# RocketometerPx_9DS0.net
KiCad netlist of a schematic drawn in EAGLE
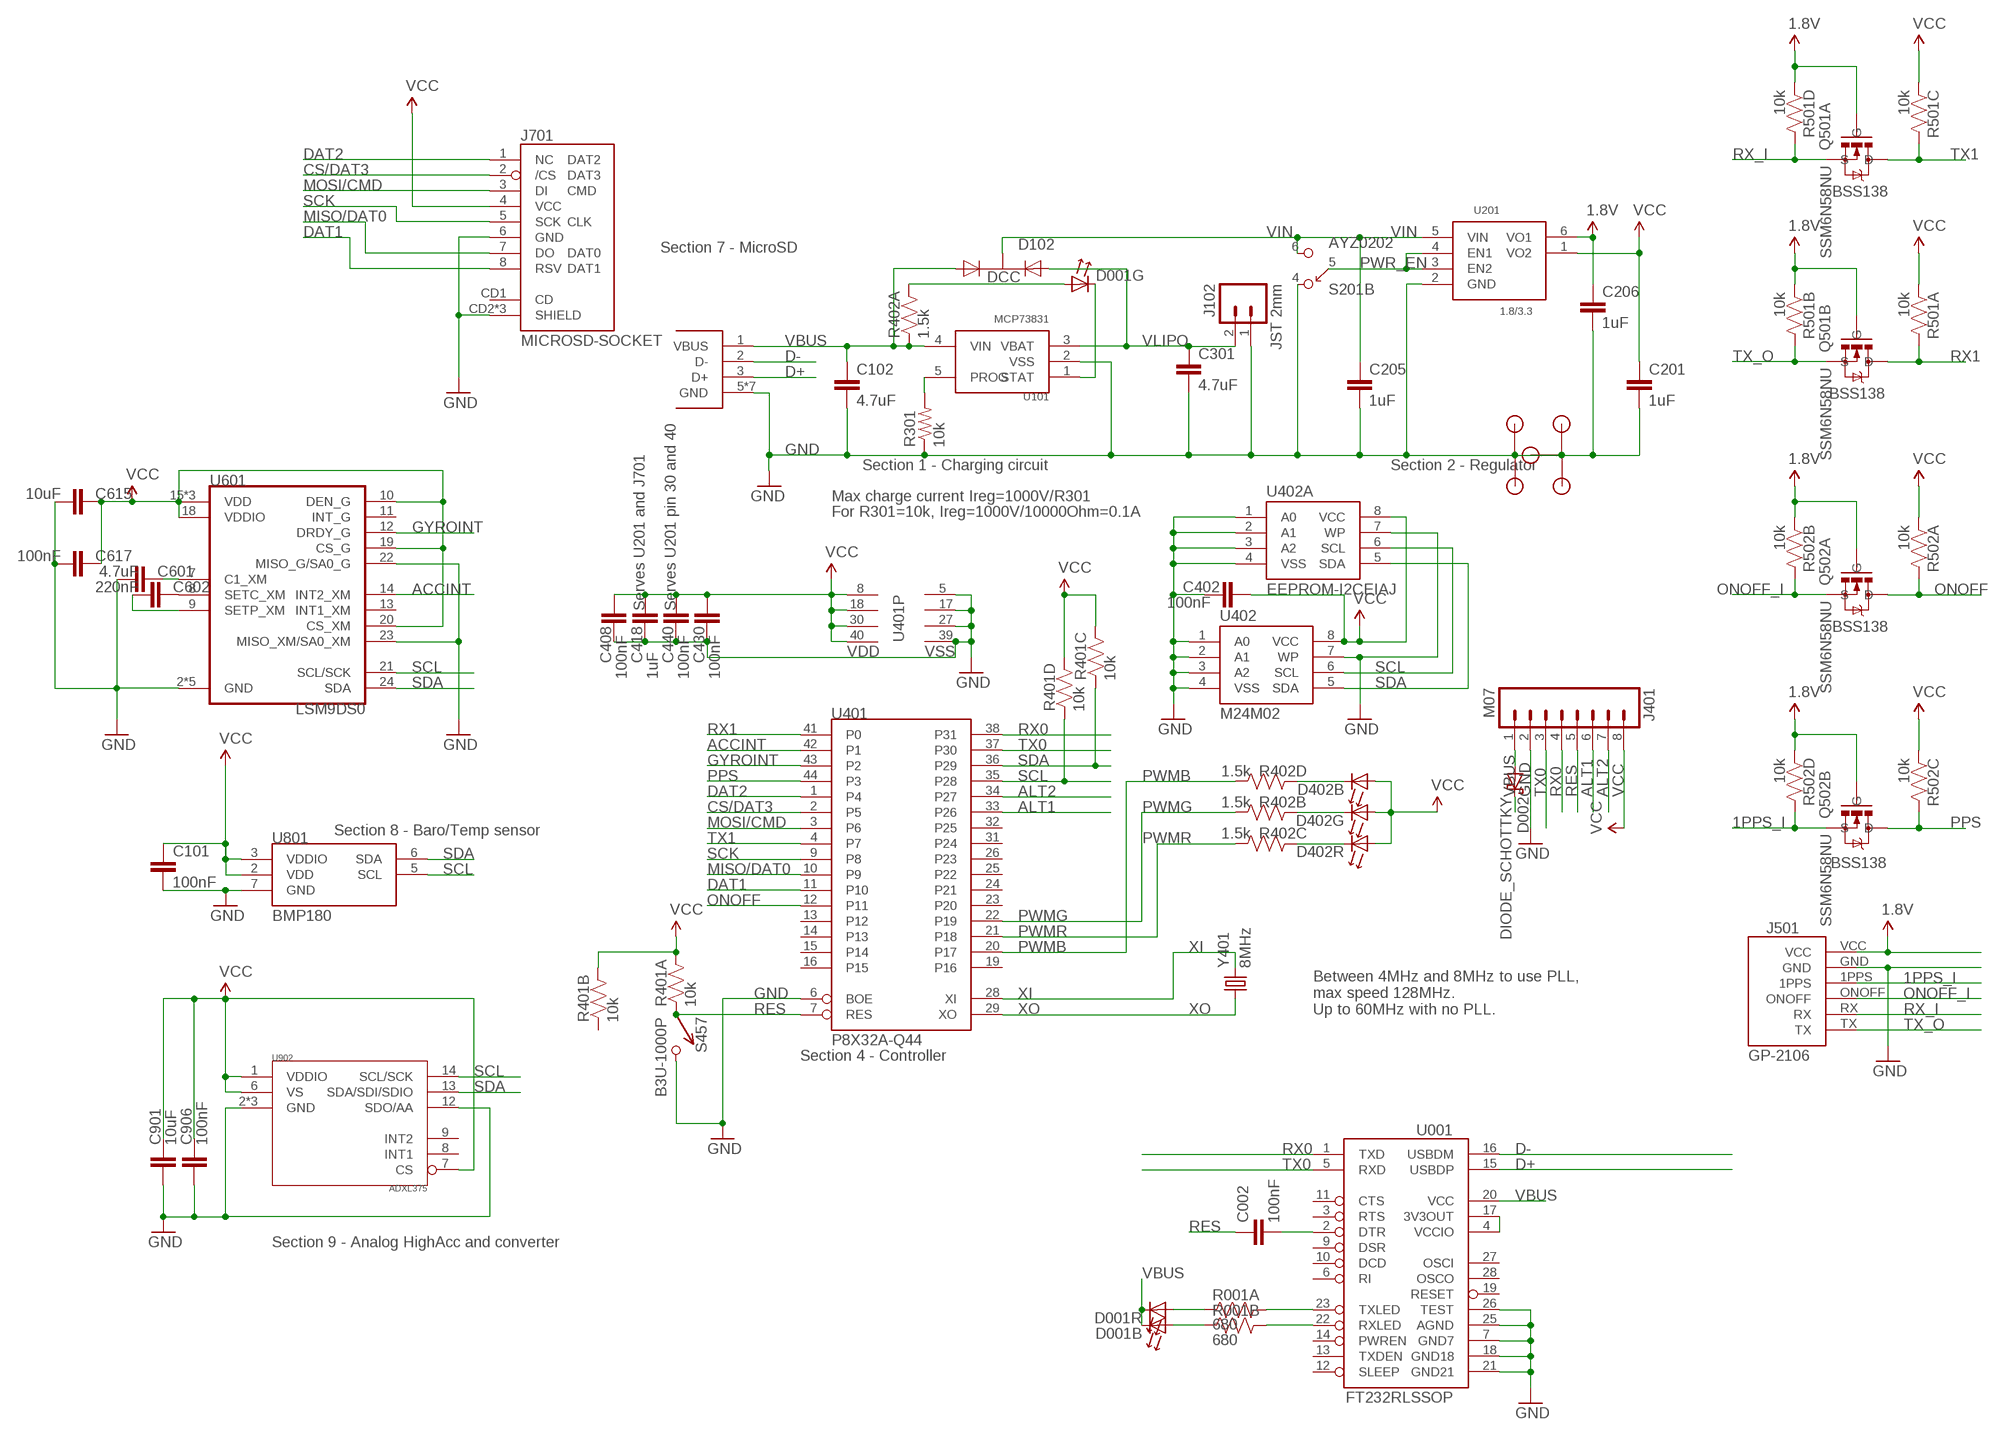
[diagram p0: schematic, sheet 1]

(export (version "E")
  (design (tool "Eeschema 10.0.6"))
  (components
    (comp (ref "C002")
      (value "100nF")
      (footprint "eagle-import:0402-CAP")
      (libsource (lib "eagle-import") (part "CAP0402-CAP"))
    )
    (comp (ref "C101")
      (value "100nF")
      (footprint "eagle-import:0402-CAP")
      (libsource (lib "eagle-import") (part "CAP0402-CAP"))
    )
    (comp (ref "C102")
      (value "4.7uF")
      (footprint "eagle-import:0402-CAP")
      (libsource (lib "eagle-import") (part "CAP0402-CAP"))
    )
    (comp (ref "C201")
      (value "1uF")
      (footprint "eagle-import:0402-CAP")
      (libsource (lib "eagle-import") (part "CAP0402-CAP"))
    )
    (comp (ref "C205")
      (value "1uF")
      (footprint "eagle-import:0402-CAP")
      (libsource (lib "eagle-import") (part "CAP0402-CAP"))
    )
    (comp (ref "C206")
      (value "1uF")
      (footprint "eagle-import:0402-CAP")
      (libsource (lib "eagle-import") (part "CAP0402-CAP"))
    )
    (comp (ref "C301")
      (value "4.7uF")
      (footprint "eagle-import:0402-CAP")
      (libsource (lib "eagle-import") (part "CAP0402-CAP"))
    )
    (comp (ref "C402")
      (value "100nF")
      (footprint "eagle-import:0402-CAP")
      (libsource (lib "eagle-import") (part "CAP0402-CAP"))
    )
    (comp (ref "C408")
      (value "100nF")
      (footprint "eagle-import:0402-CAP")
      (libsource (lib "eagle-import") (part "CAP0402-CAP"))
    )
    (comp (ref "C418")
      (value "1uF")
      (footprint "eagle-import:0402-CAP")
      (libsource (lib "eagle-import") (part "CAP0402-CAP"))
    )
    (comp (ref "C430")
      (value "100nF")
      (footprint "eagle-import:0402-CAP")
      (libsource (lib "eagle-import") (part "CAP0402-CAP"))
    )
    (comp (ref "C440")
      (value "100nF")
      (footprint "eagle-import:0402-CAP")
      (libsource (lib "eagle-import") (part "CAP0402-CAP"))
    )
    (comp (ref "C601")
      (value "4.7uF")
      (footprint "eagle-import:0402-CAP")
      (libsource (lib "eagle-import") (part "CAP0402-CAP"))
    )
    (comp (ref "C602")
      (value "220nF")
      (footprint "eagle-import:0402-CAP")
      (libsource (lib "eagle-import") (part "CAP0402-CAP"))
    )
    (comp (ref "C615")
      (value "10uF")
      (footprint "eagle-import:0603-CAP")
      (libsource (lib "eagle-import") (part "CAP0603-CAP"))
    )
    (comp (ref "C617")
      (value "100nF")
      (footprint "eagle-import:0402-CAP")
      (libsource (lib "eagle-import") (part "CAP0402-CAP"))
    )
    (comp (ref "C901")
      (value "10uF")
      (footprint "eagle-import:0603-CAP")
      (libsource (lib "eagle-import") (part "CAP0603-CAP"))
    )
    (comp (ref "C906")
      (value "100nF")
      (footprint "eagle-import:0402-CAP")
      (libsource (lib "eagle-import") (part "SparkFun-Passives_CAP0402-CAP"))
    )
    (comp (ref "D001")
      (value "SMLP36RGB2W(R)")
      (footprint "eagle-import:SMLP36")
      (libsource (lib "eagle-import") (part "SMLP36RGB2W(R)"))
    )
    (comp (ref "D002")
      (value "DIODE_SCHOTTKY")
      (footprint "eagle-import:D0603")
      (libsource (lib "eagle-import") (part "DIODE_SCHOTTKY"))
    )
    (comp (ref "D102")
      (value "DCC")
      (footprint "eagle-import:SOT-23-3")
      (libsource (lib "eagle-import") (part "PMEG2005CT"))
    )
    (comp (ref "D402")
      (value "SMLP36RGB2W(R)")
      (footprint "eagle-import:SMLP36")
      (libsource (lib "eagle-import") (part "SMLP36RGB2W(R)"))
    )
    (comp (ref "J001")
      (value "USB_MICROB_JSTFCI")
      (footprint "eagle-import:USB-MICROB-CONN-09505")
      (libsource (lib "eagle-import") (part "USB_MICROB_JSTFCI"))
    )
    (comp (ref "J102")
      (value "JST 2mm")
      (footprint "eagle-import:JST-2-SMD")
      (libsource (lib "eagle-import") (part "M02-JST-2MM-SMT"))
    )
    (comp (ref "J401")
      (value "M07")
      (footprint "eagle-import:M08SIP")
      (libsource (lib "eagle-import") (part "M08NOSILK"))
    )
    (comp (ref "J501")
      (value "GP-2106")
      (footprint "eagle-import:GP-2106")
      (libsource (lib "eagle-import") (part "GP-2106"))
    )
    (comp (ref "J701")
      (value "MICROSD-SOCKET")
      (footprint "eagle-import:MICROSD-SOCKET-PP")
      (libsource (lib "eagle-import") (part "MICROSD-SOCKET"))
    )
    (comp (ref "JP1")
      (value "STANDOFF")
      (footprint "eagle-import:STANDOFF")
      (libsource (lib "eagle-import") (part "STANDOFF"))
    )
    (comp (ref "JP2")
      (value "STANDOFF")
      (footprint "eagle-import:STANDOFF")
      (libsource (lib "eagle-import") (part "STANDOFF"))
    )
    (comp (ref "JP3")
      (value "STANDOFF")
      (footprint "eagle-import:STANDOFF")
      (libsource (lib "eagle-import") (part "STANDOFF"))
    )
    (comp (ref "JP4")
      (value "STANDOFF")
      (footprint "eagle-import:STANDOFF")
      (libsource (lib "eagle-import") (part "STANDOFF"))
    )
    (comp (ref "JP5")
      (value "STANDOFF")
      (footprint "eagle-import:STANDOFF")
      (libsource (lib "eagle-import") (part "STANDOFF"))
    )
    (comp (ref "Q501")
      (value "SSM6N58NU")
      (footprint "eagle-import:UDFN6")
      (libsource (lib "eagle-import") (part "SSM6N58NU"))
    )
    (comp (ref "Q502")
      (value "SSM6N58NU")
      (footprint "eagle-import:UDFN6")
      (libsource (lib "eagle-import") (part "SSM6N58NU"))
    )
    (comp (ref "R001")
      (value "680")
      (footprint "eagle-import:CRA02")
      (fields (field (name "DIGIKEY") "CRA4S8680CT-ND"))
      (libsource (lib "eagle-import") (part "RP2EXB24V"))
    )
    (comp (ref "R301")
      (value "10k")
      (footprint "eagle-import:0402-RES")
      (libsource (lib "eagle-import") (part "RESISTOR0402-RES"))
    )
    (comp (ref "R401")
      (value "10k")
      (footprint "eagle-import:CRA04")
      (fields (field (name "DIGIKEY") "CRA4S810KCT-ND"))
      (libsource (lib "eagle-import") (part "RP404"))
    )
    (comp (ref "R402")
      (value "1.5k")
      (footprint "eagle-import:CRA04")
      (fields (field (name "DIGIKEY") "CRA4S81.5KCT-ND"))
      (libsource (lib "eagle-import") (part "RP404"))
    )
    (comp (ref "R501")
      (value "10k")
      (footprint "eagle-import:CRA04")
      (fields (field (name "DIGIKEY") "CRA4S810KCT-ND"))
      (libsource (lib "eagle-import") (part "RP404"))
    )
    (comp (ref "R502")
      (value "10k")
      (footprint "eagle-import:CRA04")
      (fields (field (name "DIGIKEY") "CRA4S810KCT-ND"))
      (libsource (lib "eagle-import") (part "RP404"))
    )
    (comp (ref "S201")
      (value "AYZ0202")
      (footprint "eagle-import:AYZ0202")
      (libsource (lib "eagle-import") (part "AYZ0202"))
    )
    (comp (ref "S457")
      (value "B3U-1000P")
      (footprint "eagle-import:B3U-1000P")
      (libsource (lib "eagle-import") (part "B3U-1000P"))
    )
    (comp (ref "U001")
      (value "FT232RLSSOP")
      (footprint "eagle-import:SSOP28DB")
      (libsource (lib "eagle-import") (part "FT232RLSSOP"))
    )
    (comp (ref "U101")
      (value "MCP73831")
      (footprint "eagle-import:SOT-23-5")
      (libsource (lib "eagle-import") (part "MCP73831"))
    )
    (comp (ref "U201")
      (value "1.8/3.3")
      (footprint "eagle-import:SOT-23-6")
      (libsource (lib "eagle-import") (part "AP73X2"))
    )
    (comp (ref "U401")
      (value "P8X32A-Q44")
      (footprint "eagle-import:P8X32A-Q44")
      (fields (field (name "DIGIKEY") "P8X32A-Q44-ND"))
      (libsource (lib "eagle-import") (part "P8X32A-Q44"))
    )
    (comp (ref "U402")
      (value "M24M02")
      (footprint "eagle-import:SO8N")
      (libsource (lib "eagle-import") (part "EEPROM-I2C"))
    )
    (comp (ref "U402A")
      (value "EEPROM-I2CEIAJ")
      (footprint "eagle-import:SO08-EIAJ")
      (libsource (lib "eagle-import") (part "EEPROM-I2CEIAJ"))
    )
    (comp (ref "U601")
      (value "LSM9DS0")
      (footprint "eagle-import:LGA24_LSM")
      (libsource (lib "eagle-import") (part "LSM9DS0"))
    )
    (comp (ref "U801")
      (value "BMP180")
      (footprint "eagle-import:BMP180")
      (libsource (lib "eagle-import") (part "BMP180"))
    )
    (comp (ref "U902")
      (value "ADXL375")
      (footprint "eagle-import:ADXL375")
      (libsource (lib "eagle-import") (part "ADXL375"))
    )
    (comp (ref "Y401")
      (value "8MHz")
      (footprint "eagle-import:CRYSTAL_SMD_3_2MM_2_5MM")
      (libsource (lib "eagle-import") (part "NX3225GD"))
    )
  )
  (nets
    (net (code "1") (name "/1PPS_I") (class "Default")
      (node (ref "J501") (pin "1PPS") (pinfunction "1PPS_1PPS") (pintype "bidirectional"))
      (node (ref "Q502") (pin "4") (pinfunction "S_4") (pintype "passive"))
      (node (ref "R502") (pin "5") (pinfunction "2_5") (pintype "passive"))
    )
    (net (code "2") (name "/ACCINT") (class "Default")
      (node (ref "U401") (pin "42") (pinfunction "P1_42") (pintype "bidirectional"))
      (node (ref "U601") (pin "14") (pinfunction "INT2_XM_14") (pintype "bidirectional"))
    )
    (net (code "3") (name "/ALT1") (class "Default")
      (node (ref "J401") (pin "6") (pinfunction "6_6") (pintype "passive"))
      (node (ref "U401") (pin "33") (pinfunction "P26_33") (pintype "bidirectional"))
    )
    (net (code "4") (name "/ALT2") (class "Default")
      (node (ref "J401") (pin "7") (pinfunction "7_7") (pintype "passive"))
      (node (ref "U401") (pin "34") (pinfunction "P27_34") (pintype "bidirectional"))
    )
    (net (code "5") (name "/CS{slash}DAT3") (class "Default")
      (node (ref "J701") (pin "2") (pinfunction "/CS_2") (pintype "bidirectional"))
      (node (ref "U401") (pin "2") (pinfunction "P5_2") (pintype "bidirectional"))
    )
    (net (code "6") (name "/D+") (class "Default")
      (node (ref "J001") (pin "3") (pinfunction "D+_3") (pintype "bidirectional"))
      (node (ref "U001") (pin "15") (pinfunction "USBDP_15") (pintype "bidirectional"))
    )
    (net (code "7") (name "/D-") (class "Default")
      (node (ref "J001") (pin "2") (pinfunction "D-_2") (pintype "bidirectional"))
      (node (ref "U001") (pin "16") (pinfunction "USBDM_16") (pintype "bidirectional"))
    )
    (net (code "8") (name "/DAT1") (class "Default")
      (node (ref "J701") (pin "8") (pinfunction "RSV_8") (pintype "bidirectional"))
      (node (ref "U401") (pin "11") (pinfunction "P10_11") (pintype "bidirectional"))
    )
    (net (code "9") (name "/DAT2") (class "Default")
      (node (ref "J701") (pin "1") (pinfunction "NC_1") (pintype "bidirectional"))
      (node (ref "U401") (pin "1") (pinfunction "P4_1") (pintype "bidirectional"))
    )
    (net (code "10") (name "/GYROINT") (class "Default")
      (node (ref "U401") (pin "43") (pinfunction "P2_43") (pintype "bidirectional"))
      (node (ref "U601") (pin "12") (pinfunction "DRDY_G_12") (pintype "bidirectional"))
    )
    (net (code "11") (name "/MISO{slash}DAT0") (class "Default")
      (node (ref "J701") (pin "7") (pinfunction "DO_7") (pintype "bidirectional"))
      (node (ref "U401") (pin "10") (pinfunction "P9_10") (pintype "bidirectional"))
    )
    (net (code "12") (name "/MOSI{slash}CMD") (class "Default")
      (node (ref "J701") (pin "3") (pinfunction "DI_3") (pintype "bidirectional"))
      (node (ref "U401") (pin "3") (pinfunction "P6_3") (pintype "bidirectional"))
    )
    (net (code "13") (name "/ONOFF") (class "Default")
      (node (ref "Q502") (pin "6") (pinfunction "D_6") (pintype "passive"))
      (node (ref "R502") (pin "8") (pinfunction "2_8") (pintype "passive"))
      (node (ref "U401") (pin "12") (pinfunction "P11_12") (pintype "bidirectional"))
    )
    (net (code "14") (name "/ONOFF_I") (class "Default")
      (node (ref "J501") (pin "ONOFF") (pinfunction "ONOFF_ONOFF") (pintype "bidirectional"))
      (node (ref "Q502") (pin "1") (pinfunction "S_1") (pintype "passive"))
      (node (ref "R502") (pin "7") (pinfunction "2_7") (pintype "passive"))
    )
    (net (code "15") (name "/PPS") (class "Default")
      (node (ref "Q502") (pin "3") (pinfunction "D_3") (pintype "passive"))
      (node (ref "R502") (pin "6") (pinfunction "2_6") (pintype "passive"))
      (node (ref "U401") (pin "44") (pinfunction "P3_44") (pintype "bidirectional"))
    )
    (net (code "16") (name "/PWMB") (class "Default")
      (node (ref "R402") (pin "4") (pinfunction "1_4") (pintype "passive"))
      (node (ref "U401") (pin "20") (pinfunction "P17_20") (pintype "bidirectional"))
    )
    (net (code "17") (name "/PWMG") (class "Default")
      (node (ref "R402") (pin "2") (pinfunction "1_2") (pintype "passive"))
      (node (ref "U401") (pin "22") (pinfunction "P19_22") (pintype "bidirectional"))
    )
    (net (code "18") (name "/PWMR") (class "Default")
      (node (ref "R402") (pin "3") (pinfunction "1_3") (pintype "passive"))
      (node (ref "U401") (pin "21") (pinfunction "P18_21") (pintype "bidirectional"))
    )
    (net (code "19") (name "/PWR_EN") (class "Default")
      (node (ref "S201") (pin "5") (pinfunction "P$3_5") (pintype "bidirectional"))
      (node (ref "U201") (pin "3") (pinfunction "EN2_3") (pintype "bidirectional"))
      (node (ref "U201") (pin "4") (pinfunction "EN1_4") (pintype "bidirectional"))
    )
    (net (code "20") (name "/RES") (class "Default")
      (node (ref "C002") (pin "1") (pinfunction "1_1") (pintype "passive"))
      (node (ref "J401") (pin "5") (pinfunction "5_5") (pintype "passive"))
      (node (ref "R401") (pin "1") (pinfunction "1_1") (pintype "passive"))
      (node (ref "S457") (pin "P$1") (pinfunction "1_P$1") (pintype "bidirectional"))
      (node (ref "U401") (pin "7") (pinfunction "RES_7") (pintype "bidirectional"))
    )
    (net (code "21") (name "/RX0") (class "Default")
      (node (ref "J401") (pin "4") (pinfunction "4_4") (pintype "passive"))
      (node (ref "U001") (pin "1") (pinfunction "TXD_1") (pintype "output"))
      (node (ref "U401") (pin "38") (pinfunction "P31_38") (pintype "bidirectional"))
    )
    (net (code "22") (name "/RX1") (class "Default")
      (node (ref "Q501") (pin "3") (pinfunction "D_3") (pintype "passive"))
      (node (ref "R501") (pin "8") (pinfunction "2_8") (pintype "passive"))
      (node (ref "U401") (pin "41") (pinfunction "P0_41") (pintype "bidirectional"))
    )
    (net (code "23") (name "/RX_I") (class "Default")
      (node (ref "J501") (pin "RX") (pinfunction "RX_RX") (pintype "bidirectional"))
      (node (ref "Q501") (pin "1") (pinfunction "S_1") (pintype "passive"))
      (node (ref "R501") (pin "5") (pinfunction "2_5") (pintype "passive"))
    )
    (net (code "24") (name "/SCK") (class "Default")
      (node (ref "J701") (pin "5") (pinfunction "SCK_5") (pintype "bidirectional"))
      (node (ref "U401") (pin "9") (pinfunction "P8_9") (pintype "bidirectional"))
    )
    (net (code "25") (name "/SCL") (class "Default")
      (node (ref "R401") (pin "4") (pinfunction "1_4") (pintype "passive"))
      (node (ref "U401") (pin "35") (pinfunction "P28_35") (pintype "bidirectional"))
      (node (ref "U402") (pin "6") (pinfunction "SCL_6") (pintype "bidirectional"))
      (node (ref "U402A") (pin "6") (pinfunction "SCL_6") (pintype "bidirectional"))
      (node (ref "U601") (pin "21") (pinfunction "SCL/SCK_21") (pintype "bidirectional"))
      (node (ref "U801") (pin "5") (pinfunction "SCL_5") (pintype "input"))
      (node (ref "U902") (pin "14") (pinfunction "SCL/SCK_14") (pintype "input"))
    )
    (net (code "26") (name "/SDA") (class "Default")
      (node (ref "R401") (pin "3") (pinfunction "1_3") (pintype "passive"))
      (node (ref "U401") (pin "36") (pinfunction "P29_36") (pintype "bidirectional"))
      (node (ref "U402") (pin "5") (pinfunction "SDA_5") (pintype "bidirectional"))
      (node (ref "U402A") (pin "5") (pinfunction "SDA_5") (pintype "bidirectional"))
      (node (ref "U601") (pin "24") (pinfunction "SDA_24") (pintype "bidirectional"))
      (node (ref "U801") (pin "6") (pinfunction "SDA_6") (pintype "bidirectional"))
      (node (ref "U902") (pin "13") (pinfunction "SDA/SDI/SDIO_13") (pintype "bidirectional"))
    )
    (net (code "27") (name "/TX0") (class "Default")
      (node (ref "J401") (pin "3") (pinfunction "3_3") (pintype "passive"))
      (node (ref "U001") (pin "5") (pinfunction "RXD_5") (pintype "input"))
      (node (ref "U401") (pin "37") (pinfunction "P30_37") (pintype "bidirectional"))
    )
    (net (code "28") (name "/TX1") (class "Default")
      (node (ref "Q501") (pin "6") (pinfunction "D_6") (pintype "passive"))
      (node (ref "R501") (pin "6") (pinfunction "2_6") (pintype "passive"))
      (node (ref "U401") (pin "4") (pinfunction "P7_4") (pintype "bidirectional"))
    )
    (net (code "29") (name "/TX_O") (class "Default")
      (node (ref "J501") (pin "TX") (pinfunction "TX_TX") (pintype "bidirectional"))
      (node (ref "Q501") (pin "4") (pinfunction "S_4") (pintype "passive"))
      (node (ref "R501") (pin "7") (pinfunction "2_7") (pintype "passive"))
    )
    (net (code "30") (name "/VBUS") (class "Default")
      (node (ref "C102") (pin "1") (pinfunction "1_1") (pintype "passive"))
      (node (ref "D001") (pin "1") (pinfunction "C_1") (pintype "passive"))
      (node (ref "D001") (pin "3") (pinfunction "C_3") (pintype "passive"))
      (node (ref "D002") (pin "C") (pinfunction "K_C") (pintype "passive"))
      (node (ref "D102") (pin "1") (pinfunction "A1_1") (pintype "passive"))
      (node (ref "J001") (pin "1") (pinfunction "VBUS_1") (pintype "bidirectional"))
      (node (ref "R402") (pin "1") (pinfunction "1_1") (pintype "passive"))
      (node (ref "U001") (pin "20") (pinfunction "VCC_20") (pintype "power_in"))
      (node (ref "U101") (pin "4") (pinfunction "VIN_4") (pintype "power_in"))
    )
    (net (code "31") (name "/VIN") (class "Default")
      (node (ref "C205") (pin "1") (pinfunction "1_1") (pintype "passive"))
      (node (ref "D102") (pin "3") (pinfunction "K_3") (pintype "passive"))
      (node (ref "S201") (pin "6") (pinfunction "P$2_6") (pintype "bidirectional"))
      (node (ref "U201") (pin "5") (pinfunction "VIN_5") (pintype "bidirectional"))
    )
    (net (code "32") (name "/VLIPO") (class "Default")
      (node (ref "C301") (pin "1") (pinfunction "1_1") (pintype "passive"))
      (node (ref "D102") (pin "2") (pinfunction "A2_2") (pintype "passive"))
      (node (ref "J102") (pin "2") (pinfunction "2_2") (pintype "passive"))
      (node (ref "U101") (pin "3") (pinfunction "VBAT_3") (pintype "power_in"))
    )
    (net (code "33") (name "/XI") (class "Default")
      (node (ref "U401") (pin "28") (pinfunction "XI_28") (pintype "input"))
      (node (ref "Y401") (pin "2") (pinfunction "2_2") (pintype "passive"))
    )
    (net (code "34") (name "/XO") (class "Default")
      (node (ref "U401") (pin "29") (pinfunction "XO_29") (pintype "output"))
      (node (ref "Y401") (pin "1") (pinfunction "1_1") (pintype "passive"))
    )
    (net (code "35") (name "1.8V") (class "Default")
      (node (ref "C206") (pin "1") (pinfunction "1_1") (pintype "passive"))
      (node (ref "J501") (pin "VCC") (pinfunction "VCC_VCC") (pintype "bidirectional"))
      (node (ref "Q501") (pin "2") (pinfunction "G_2") (pintype "passive"))
      (node (ref "Q501") (pin "5") (pinfunction "G_5") (pintype "passive"))
      (node (ref "Q502") (pin "2") (pinfunction "G_2") (pintype "passive"))
      (node (ref "Q502") (pin "5") (pinfunction "G_5") (pintype "passive"))
      (node (ref "R501") (pin "2") (pinfunction "1_2") (pintype "passive"))
      (node (ref "R501") (pin "4") (pinfunction "1_4") (pintype "passive"))
      (node (ref "R502") (pin "2") (pinfunction "1_2") (pintype "passive"))
      (node (ref "R502") (pin "4") (pinfunction "1_4") (pintype "passive"))
      (node (ref "U201") (pin "6") (pinfunction "VO1_6") (pintype "bidirectional"))
    )
    (net (code "36") (name "GND") (class "Default")
      (node (ref "C101") (pin "2") (pinfunction "2_2") (pintype "passive"))
      (node (ref "C102") (pin "2") (pinfunction "2_2") (pintype "passive"))
      (node (ref "C201") (pin "2") (pinfunction "2_2") (pintype "passive"))
      (node (ref "C205") (pin "2") (pinfunction "2_2") (pintype "passive"))
      (node (ref "C206") (pin "2") (pinfunction "2_2") (pintype "passive"))
      (node (ref "C301") (pin "2") (pinfunction "2_2") (pintype "passive"))
      (node (ref "C402") (pin "2") (pinfunction "2_2") (pintype "passive"))
      (node (ref "C408") (pin "2") (pinfunction "2_2") (pintype "passive"))
      (node (ref "C418") (pin "2") (pinfunction "2_2") (pintype "passive"))
      (node (ref "C430") (pin "2") (pinfunction "2_2") (pintype "passive"))
      (node (ref "C440") (pin "2") (pinfunction "2_2") (pintype "passive"))
      (node (ref "C601") (pin "2") (pinfunction "2_2") (pintype "passive"))
      (node (ref "C615") (pin "1") (pinfunction "1_1") (pintype "passive"))
      (node (ref "C617") (pin "1") (pinfunction "1_1") (pintype "passive"))
      (node (ref "C901") (pin "2") (pinfunction "2_2") (pintype "passive"))
      (node (ref "C906") (pin "2") (pinfunction "2_2") (pintype "passive"))
      (node (ref "J001") (pin "5") (pinfunction "GND_5") (pintype "bidirectional"))
      (node (ref "J001") (pin "P1") (pinfunction "GND_P1") (pintype "bidirectional"))
      (node (ref "J001") (pin "P2") (pinfunction "GND_P2") (pintype "bidirectional"))
      (node (ref "J001") (pin "P3") (pinfunction "GND_P3") (pintype "bidirectional"))
      (node (ref "J001") (pin "P4") (pinfunction "GND_P4") (pintype "bidirectional"))
      (node (ref "J001") (pin "P5") (pinfunction "GND_P5") (pintype "bidirectional"))
      (node (ref "J001") (pin "P6") (pinfunction "GND_P6") (pintype "bidirectional"))
      (node (ref "J102") (pin "1") (pinfunction "1_1") (pintype "passive"))
      (node (ref "J401") (pin "2") (pinfunction "2_2") (pintype "passive"))
      (node (ref "J501") (pin "GND") (pinfunction "GND_GND") (pintype "bidirectional"))
      (node (ref "J701") (pin "6") (pinfunction "GND_6") (pintype "bidirectional"))
      (node (ref "J701") (pin "CD2") (pinfunction "SHIELD_CD2") (pintype "bidirectional"))
      (node (ref "J701") (pin "GND1") (pinfunction "SHIELD_GND1") (pintype "bidirectional"))
      (node (ref "J701") (pin "GND3") (pinfunction "SHIELD_GND3") (pintype "bidirectional"))
      (node (ref "JP1") (pin "P$1") (pinfunction "P$1_P$1") (pintype "bidirectional"))
      (node (ref "JP2") (pin "P$1") (pinfunction "P$1_P$1") (pintype "bidirectional"))
      (node (ref "JP3") (pin "P$1") (pinfunction "P$1_P$1") (pintype "bidirectional"))
      (node (ref "JP4") (pin "P$1") (pinfunction "P$1_P$1") (pintype "bidirectional"))
      (node (ref "JP5") (pin "P$1") (pinfunction "P$1_P$1") (pintype "bidirectional"))
      (node (ref "R301") (pin "1") (pinfunction "1_1") (pintype "passive"))
      (node (ref "S201") (pin "4") (pinfunction "P$1_4") (pintype "bidirectional"))
      (node (ref "S457") (pin "P$2") (pinfunction "2_P$2") (pintype "bidirectional"))
      (node (ref "U001") (pin "18") (pinfunction "GND18_18") (pintype "power_in"))
      (node (ref "U001") (pin "21") (pinfunction "GND21_21") (pintype "power_in"))
      (node (ref "U001") (pin "25") (pinfunction "AGND_25") (pintype "power_in"))
      (node (ref "U001") (pin "26") (pinfunction "TEST_26") (pintype "input"))
      (node (ref "U001") (pin "7") (pinfunction "GND7_7") (pintype "power_in"))
      (node (ref "U101") (pin "2") (pinfunction "VSS_2") (pintype "power_in"))
      (node (ref "U201") (pin "2") (pinfunction "GND_2") (pintype "bidirectional"))
      (node (ref "U401") (pin "17") (pinfunction "VSS_17") (pintype "power_in"))
      (node (ref "U401") (pin "27") (pinfunction "VSS_27") (pintype "power_in"))
      (node (ref "U401") (pin "39") (pinfunction "VSS_39") (pintype "power_in"))
      (node (ref "U401") (pin "5") (pinfunction "VSS_5") (pintype "power_in"))
      (node (ref "U401") (pin "6") (pinfunction "BOE_6") (pintype "input"))
      (node (ref "U402") (pin "1") (pinfunction "A0_1") (pintype "bidirectional"))
      (node (ref "U402") (pin "2") (pinfunction "A1_2") (pintype "bidirectional"))
      (node (ref "U402") (pin "3") (pinfunction "A2_3") (pintype "bidirectional"))
      (node (ref "U402") (pin "4") (pinfunction "VSS_4") (pintype "power_in"))
      (node (ref "U402") (pin "7") (pinfunction "WP_7") (pintype "bidirectional"))
      (node (ref "U402A") (pin "1") (pinfunction "A0_1") (pintype "bidirectional"))
      (node (ref "U402A") (pin "2") (pinfunction "A1_2") (pintype "bidirectional"))
      (node (ref "U402A") (pin "3") (pinfunction "A2_3") (pintype "bidirectional"))
      (node (ref "U402A") (pin "4") (pinfunction "VSS_4") (pintype "power_in"))
      (node (ref "U402A") (pin "7") (pinfunction "WP_7") (pintype "bidirectional"))
      (node (ref "U601") (pin "2") (pinfunction "GND_2") (pintype "power_in"))
      (node (ref "U601") (pin "22") (pinfunction "MISO_G/SA0_G_22") (pintype "bidirectional"))
      (node (ref "U601") (pin "23") (pinfunction "MISO_XM/SA0_XM_23") (pintype "bidirectional"))
      (node (ref "U601") (pin "3") (pinfunction "GND_3") (pintype "power_in"))
      (node (ref "U601") (pin "4") (pinfunction "GND_4") (pintype "power_in"))
      (node (ref "U601") (pin "5") (pinfunction "GND_5") (pintype "power_in"))
      (node (ref "U601") (pin "6") (pinfunction "GND_6") (pintype "power_in"))
      (node (ref "U801") (pin "7") (pinfunction "GND_7") (pintype "power_in"))
      (node (ref "U902") (pin "12") (pinfunction "SDO/AA_12") (pintype "bidirectional"))
      (node (ref "U902") (pin "2") (pinfunction "GND_2") (pintype "power_in"))
      (node (ref "U902") (pin "4") (pinfunction "GND_4") (pintype "power_in"))
      (node (ref "U902") (pin "5") (pinfunction "GND_5") (pintype "power_in"))
    )
    (net (code "37") (name "Net-(D001A-A)") (class "Default")
      (node (ref "D001") (pin "2") (pinfunction "A_2") (pintype "passive"))
      (node (ref "R001") (pin "2") (pinfunction "1_2") (pintype "passive"))
    )
    (net (code "38") (name "Net-(D001B-A)") (class "Default")
      (node (ref "D001") (pin "6") (pinfunction "A_6") (pintype "passive"))
      (node (ref "R402") (pin "8") (pinfunction "2_8") (pintype "passive"))
    )
    (net (code "39") (name "Net-(D001B-C)") (class "Default")
      (node (ref "D001") (pin "5") (pinfunction "C_5") (pintype "passive"))
      (node (ref "U101") (pin "1") (pinfunction "STAT_1") (pintype "bidirectional"))
    )
    (net (code "40") (name "Net-(D001C-A)") (class "Default")
      (node (ref "D001") (pin "4") (pinfunction "A_4") (pintype "passive"))
      (node (ref "R001") (pin "1") (pinfunction "1_1") (pintype "passive"))
    )
    (net (code "41") (name "Net-(D002-PadA)") (class "Default")
      (node (ref "D002") (pin "A") (pinfunction "A_A") (pintype "passive"))
      (node (ref "J401") (pin "1") (pinfunction "1_1") (pintype "passive"))
    )
    (net (code "42") (name "Net-(D402A-C)") (class "Default")
      (node (ref "D402") (pin "1") (pinfunction "C_1") (pintype "passive"))
      (node (ref "R402") (pin "5") (pinfunction "2_5") (pintype "passive"))
    )
    (net (code "43") (name "Net-(D402B-C)") (class "Default")
      (node (ref "D402") (pin "5") (pinfunction "C_5") (pintype "passive"))
      (node (ref "R402") (pin "7") (pinfunction "2_7") (pintype "passive"))
    )
    (net (code "44") (name "Net-(D402C-C)") (class "Default")
      (node (ref "D402") (pin "3") (pinfunction "C_3") (pintype "passive"))
      (node (ref "R402") (pin "6") (pinfunction "2_6") (pintype "passive"))
    )
    (net (code "45") (name "Net-(R001A-2)") (class "Default")
      (node (ref "R001") (pin "4") (pinfunction "2_4") (pintype "passive"))
      (node (ref "U001") (pin "23") (pinfunction "TXLED_23") (pintype "input"))
    )
    (net (code "46") (name "Net-(R001B-2)") (class "Default")
      (node (ref "R001") (pin "3") (pinfunction "2_3") (pintype "passive"))
      (node (ref "U001") (pin "22") (pinfunction "RXLED_22") (pintype "input"))
    )
    (net (code "47") (name "Net-(U001-3V3OUT)") (class "Default")
      (node (ref "U001") (pin "17") (pinfunction "3V3OUT_17") (pintype "output"))
      (node (ref "U001") (pin "4") (pinfunction "VCCIO_4") (pintype "power_in"))
    )
    (net (code "48") (name "Net-(U001-DTR)") (class "Default")
      (node (ref "C002") (pin "2") (pinfunction "2_2") (pintype "passive"))
      (node (ref "U001") (pin "2") (pinfunction "DTR_2") (pintype "output"))
    )
    (net (code "49") (name "Net-(U101-PROG)") (class "Default")
      (node (ref "R301") (pin "2") (pinfunction "2_2") (pintype "passive"))
      (node (ref "U101") (pin "5") (pinfunction "PROG_5") (pintype "passive"))
    )
    (net (code "50") (name "Net-(U601-C1_XM)") (class "Default")
      (node (ref "C601") (pin "1") (pinfunction "1_1") (pintype "passive"))
      (node (ref "U601") (pin "7") (pinfunction "C1_XM_7") (pintype "passive"))
    )
    (net (code "51") (name "Net-(U601-SETC_XM)") (class "Default")
      (node (ref "C602") (pin "1") (pinfunction "1_1") (pintype "passive"))
      (node (ref "U601") (pin "8") (pinfunction "SETC_XM_8") (pintype "passive"))
    )
    (net (code "52") (name "Net-(U601-SETP_XM)") (class "Default")
      (node (ref "C602") (pin "2") (pinfunction "2_2") (pintype "passive"))
      (node (ref "U601") (pin "9") (pinfunction "SETP_XM_9") (pintype "passive"))
    )
    (net (code "53") (name "VCC") (class "Default")
      (node (ref "C101") (pin "1") (pinfunction "1_1") (pintype "passive"))
      (node (ref "C201") (pin "1") (pinfunction "1_1") (pintype "passive"))
      (node (ref "C402") (pin "1") (pinfunction "1_1") (pintype "passive"))
      (node (ref "C408") (pin "1") (pinfunction "1_1") (pintype "passive"))
      (node (ref "C418") (pin "1") (pinfunction "1_1") (pintype "passive"))
      (node (ref "C430") (pin "1") (pinfunction "1_1") (pintype "passive"))
      (node (ref "C440") (pin "1") (pinfunction "1_1") (pintype "passive"))
      (node (ref "C615") (pin "2") (pinfunction "2_2") (pintype "passive"))
      (node (ref "C617") (pin "2") (pinfunction "2_2") (pintype "passive"))
      (node (ref "C901") (pin "1") (pinfunction "1_1") (pintype "passive"))
      (node (ref "C906") (pin "1") (pinfunction "1_1") (pintype "passive"))
      (node (ref "D402") (pin "2") (pinfunction "A_2") (pintype "passive"))
      (node (ref "D402") (pin "4") (pinfunction "A_4") (pintype "passive"))
      (node (ref "D402") (pin "6") (pinfunction "A_6") (pintype "passive"))
      (node (ref "J401") (pin "8") (pinfunction "8_8") (pintype "passive"))
      (node (ref "J701") (pin "4") (pinfunction "VCC_4") (pintype "bidirectional"))
      (node (ref "R401") (pin "5") (pinfunction "2_5") (pintype "passive"))
      (node (ref "R401") (pin "6") (pinfunction "2_6") (pintype "passive"))
      (node (ref "R401") (pin "7") (pinfunction "2_7") (pintype "passive"))
      (node (ref "R401") (pin "8") (pinfunction "2_8") (pintype "passive"))
      (node (ref "R501") (pin "1") (pinfunction "1_1") (pintype "passive"))
      (node (ref "R501") (pin "3") (pinfunction "1_3") (pintype "passive"))
      (node (ref "R502") (pin "1") (pinfunction "1_1") (pintype "passive"))
      (node (ref "R502") (pin "3") (pinfunction "1_3") (pintype "passive"))
      (node (ref "U201") (pin "1") (pinfunction "VO2_1") (pintype "bidirectional"))
      (node (ref "U401") (pin "18") (pinfunction "VDD_18") (pintype "power_in"))
      (node (ref "U401") (pin "30") (pinfunction "VDD_30") (pintype "power_in"))
      (node (ref "U401") (pin "40") (pinfunction "VDD_40") (pintype "power_in"))
      (node (ref "U401") (pin "8") (pinfunction "VDD_8") (pintype "power_in"))
      (node (ref "U402") (pin "8") (pinfunction "VCC_8") (pintype "power_in"))
      (node (ref "U402A") (pin "8") (pinfunction "VCC_8") (pintype "power_in"))
      (node (ref "U601") (pin "10") (pinfunction "DEN_G_10") (pintype "bidirectional"))
      (node (ref "U601") (pin "15") (pinfunction "VDD_15") (pintype "power_in"))
      (node (ref "U601") (pin "16") (pinfunction "VDD_16") (pintype "power_in"))
      (node (ref "U601") (pin "17") (pinfunction "VDD_17") (pintype "power_in"))
      (node (ref "U601") (pin "18") (pinfunction "VDDIO_18") (pintype "power_in"))
      (node (ref "U601") (pin "19") (pinfunction "CS_G_19") (pintype "bidirectional"))
      (node (ref "U601") (pin "20") (pinfunction "CS_XM_20") (pintype "bidirectional"))
      (node (ref "U801") (pin "2") (pinfunction "VDD_2") (pintype "power_in"))
      (node (ref "U801") (pin "3") (pinfunction "VDDIO_3") (pintype "power_in"))
      (node (ref "U902") (pin "1") (pinfunction "VDDIO_1") (pintype "power_in"))
      (node (ref "U902") (pin "6") (pinfunction "VS_6") (pintype "power_in"))
      (node (ref "U902") (pin "7") (pinfunction "CS_7") (pintype "input"))
    )
    (net (code "54") (name "unconnected-(J701-CD-PadCD1)") (class "Default")
      (node (ref "J701") (pin "CD1") (pinfunction "CD_CD1") (pintype "bidirectional"))
    )
    (net (code "55") (name "unconnected-(R401B-1-Pad2)") (class "Default")
      (node (ref "R401") (pin "2") (pinfunction "1_2") (pintype "passive"))
    )
    (net (code "56") (name "unconnected-(U001-CTS-Pad11)") (class "Default")
      (node (ref "U001") (pin "11") (pinfunction "CTS_11") (pintype "input"))
    )
    (net (code "57") (name "unconnected-(U001-DCD-Pad10)") (class "Default")
      (node (ref "U001") (pin "10") (pinfunction "DCD_10") (pintype "input"))
    )
    (net (code "58") (name "unconnected-(U001-DSR-Pad9)") (class "Default")
      (node (ref "U001") (pin "9") (pinfunction "DSR_9") (pintype "input"))
    )
    (net (code "59") (name "unconnected-(U001-OSCI-Pad27)") (class "Default")
      (node (ref "U001") (pin "27") (pinfunction "OSCI_27") (pintype "input"))
    )
    (net (code "60") (name "unconnected-(U001-OSCO-Pad28)") (class "Default")
      (node (ref "U001") (pin "28") (pinfunction "OSCO_28") (pintype "output"))
    )
    (net (code "61") (name "unconnected-(U001-PWREN-Pad14)") (class "Default")
      (node (ref "U001") (pin "14") (pinfunction "PWREN_14") (pintype "input"))
    )
    (net (code "62") (name "unconnected-(U001-RESET-Pad19)") (class "Default")
      (node (ref "U001") (pin "19") (pinfunction "RESET_19") (pintype "input"))
    )
    (net (code "63") (name "unconnected-(U001-RI-Pad6)") (class "Default")
      (node (ref "U001") (pin "6") (pinfunction "RI_6") (pintype "input"))
    )
    (net (code "64") (name "unconnected-(U001-RTS-Pad3)") (class "Default")
      (node (ref "U001") (pin "3") (pinfunction "RTS_3") (pintype "output"))
    )
    (net (code "65") (name "unconnected-(U001-SLEEP-Pad12)") (class "Default")
      (node (ref "U001") (pin "12") (pinfunction "SLEEP_12") (pintype "input"))
    )
    (net (code "66") (name "unconnected-(U001-TXDEN-Pad13)") (class "Default")
      (node (ref "U001") (pin "13") (pinfunction "TXDEN_13") (pintype "input"))
    )
    (net (code "67") (name "unconnected-(U401B-P12-Pad13)") (class "Default")
      (node (ref "U401") (pin "13") (pinfunction "P12_13") (pintype "bidirectional"))
    )
    (net (code "68") (name "unconnected-(U401B-P13-Pad14)") (class "Default")
      (node (ref "U401") (pin "14") (pinfunction "P13_14") (pintype "bidirectional"))
    )
    (net (code "69") (name "unconnected-(U401B-P14-Pad15)") (class "Default")
      (node (ref "U401") (pin "15") (pinfunction "P14_15") (pintype "bidirectional"))
    )
    (net (code "70") (name "unconnected-(U401B-P15-Pad16)") (class "Default")
      (node (ref "U401") (pin "16") (pinfunction "P15_16") (pintype "bidirectional"))
    )
    (net (code "71") (name "unconnected-(U401B-P16-Pad19)") (class "Default")
      (node (ref "U401") (pin "19") (pinfunction "P16_19") (pintype "bidirectional"))
    )
    (net (code "72") (name "unconnected-(U401B-P20-Pad23)") (class "Default")
      (node (ref "U401") (pin "23") (pinfunction "P20_23") (pintype "bidirectional"))
    )
    (net (code "73") (name "unconnected-(U401B-P21-Pad24)") (class "Default")
      (node (ref "U401") (pin "24") (pinfunction "P21_24") (pintype "bidirectional"))
    )
    (net (code "74") (name "unconnected-(U401B-P22-Pad25)") (class "Default")
      (node (ref "U401") (pin "25") (pinfunction "P22_25") (pintype "bidirectional"))
    )
    (net (code "75") (name "unconnected-(U401B-P23-Pad26)") (class "Default")
      (node (ref "U401") (pin "26") (pinfunction "P23_26") (pintype "bidirectional"))
    )
    (net (code "76") (name "unconnected-(U401B-P24-Pad31)") (class "Default")
      (node (ref "U401") (pin "31") (pinfunction "P24_31") (pintype "bidirectional"))
    )
    (net (code "77") (name "unconnected-(U401B-P25-Pad32)") (class "Default")
      (node (ref "U401") (pin "32") (pinfunction "P25_32") (pintype "bidirectional"))
    )
    (net (code "78") (name "unconnected-(U601-INT1_XM-Pad13)") (class "Default")
      (node (ref "U601") (pin "13") (pinfunction "INT1_XM_13") (pintype "bidirectional"))
    )
    (net (code "79") (name "unconnected-(U601-INT_G-Pad11)") (class "Default")
      (node (ref "U601") (pin "11") (pinfunction "INT_G_11") (pintype "bidirectional"))
    )
    (net (code "80") (name "unconnected-(U902-INT1-Pad8)") (class "Default")
      (node (ref "U902") (pin "8") (pinfunction "INT1_8") (pintype "output"))
    )
    (net (code "81") (name "unconnected-(U902-INT2-Pad9)") (class "Default")
      (node (ref "U902") (pin "9") (pinfunction "INT2_9") (pintype "output"))
    )
  )
)
